# Sheet2.net
KiCad netlist of a schematic drawn in Altium Designer
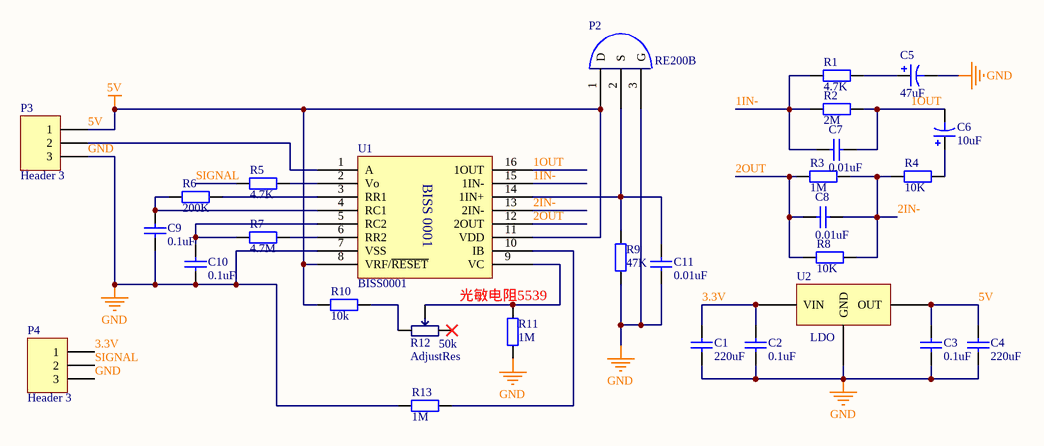
[diagram p0: Sheet2.SchDoc]

(export (version "E")
  (design (tool "Eeschema 10.0.6"))
  (components
    (comp (ref "C1")
      (value "220uF")
      (footprint "8*12")
      (description "Capacitor")
      (fields (field (name "Comment") "Cap") (field (name "PUBLISHER") "Altium Limited"))
      (libsource (lib "Miscellaneous Devices") (part "Cap"))
    )
    (comp (ref "C2")
      (value "0.1uF")
      (footprint "0603")
      (description "Capacitor")
      (fields (field (name "Comment") "Cap") (field (name "PUBLISHER") "Altium Limited"))
      (libsource (lib "Miscellaneous Devices") (part "Cap"))
    )
    (comp (ref "C3")
      (value "0.1uF")
      (footprint "0603")
      (description "Capacitor")
      (fields (field (name "Comment") "Cap") (field (name "PUBLISHER") "Altium Limited"))
      (libsource (lib "Miscellaneous Devices") (part "Cap"))
    )
    (comp (ref "C4")
      (value "220uF")
      (footprint "8*12")
      (description "Capacitor")
      (fields (field (name "Comment") "Cap") (field (name "PUBLISHER") "Altium Limited"))
      (libsource (lib "Miscellaneous Devices") (part "Cap"))
    )
    (comp (ref "C5")
      (value "47uF")
      (footprint "1210")
      (description "Polarized Capacitor (Radial)")
      (fields (field (name "Comment") "Cap Pol1") (field (name "PUBLISHER") "Altium Limited"))
      (libsource (lib "Miscellaneous Devices") (part "Cap Pol1"))
    )
    (comp (ref "C6")
      (value "10uF")
      (footprint "1206")
      (description "Polarized Capacitor (Radial)")
      (fields (field (name "Comment") "Cap Pol1") (field (name "PUBLISHER") "Altium Limited"))
      (libsource (lib "Miscellaneous Devices") (part "Cap Pol1"))
    )
    (comp (ref "C7")
      (value "0.01uF")
      (footprint "0603")
      (description "Capacitor")
      (fields (field (name "Comment") "Cap") (field (name "PUBLISHER") "Altium Limited"))
      (libsource (lib "Miscellaneous Devices") (part "Cap"))
    )
    (comp (ref "C8")
      (value "0.01uF")
      (footprint "0603")
      (description "Capacitor")
      (fields (field (name "Comment") "Cap") (field (name "PUBLISHER") "Altium Limited"))
      (libsource (lib "Miscellaneous Devices") (part "Cap"))
    )
    (comp (ref "C9")
      (value "0.1uF")
      (footprint "0603")
      (description "Capacitor")
      (fields (field (name "Comment") "Cap") (field (name "PUBLISHER") "Altium Limited"))
      (libsource (lib "Miscellaneous Devices") (part "Cap"))
    )
    (comp (ref "C10")
      (value "0.1uF")
      (footprint "0603")
      (description "Capacitor")
      (fields (field (name "Comment") "Cap") (field (name "PUBLISHER") "Altium Limited"))
      (libsource (lib "Miscellaneous Devices") (part "Cap"))
    )
    (comp (ref "C11")
      (value "0.01uF")
      (footprint "0603")
      (description "Capacitor")
      (fields (field (name "Comment") "Cap") (field (name "PUBLISHER") "Altium Limited"))
      (libsource (lib "Miscellaneous Devices") (part "Cap"))
    )
    (comp (ref "P2")
      (value "RE200B")
      (footprint "RE200B")
      (description "Infrared Sensor")
      (libsource (lib "Schlib1") (part "RE200B"))
    )
    (comp (ref "P3")
      (value "Header 3")
      (footprint "HDR1X3")
      (description "Header, 3-Pin")
      (fields (field (name "PUBLISHER") "Altium Limited"))
      (libsource (lib "Miscellaneous Connectors") (part "Header 3"))
    )
    (comp (ref "P4")
      (value "Header 3")
      (footprint "HDR1X3")
      (description "Header, 3-Pin")
      (fields (field (name "PUBLISHER") "Altium Limited"))
      (libsource (lib "Miscellaneous Connectors") (part "Header 3"))
    )
    (comp (ref "R1")
      (value "4.7K")
      (footprint "0603")
      (description "Resistor")
      (fields (field (name "Comment") "Res2") (field (name "PUBLISHER") "Altium Limited"))
      (libsource (lib "") (part "Res2_1"))
    )
    (comp (ref "R2")
      (value "2M")
      (footprint "0603")
      (description "Resistor")
      (fields (field (name "Comment") "Res2") (field (name "PUBLISHER") "Altium Limited"))
      (libsource (lib "") (part "Res2_1"))
    )
    (comp (ref "R3")
      (value "1M")
      (footprint "0603")
      (description "Resistor")
      (fields (field (name "Comment") "Res2") (field (name "PUBLISHER") "Altium Limited"))
      (libsource (lib "") (part "Res2_1"))
    )
    (comp (ref "R4")
      (value "10K")
      (footprint "0603")
      (description "Resistor")
      (fields (field (name "Comment") "Res2") (field (name "PUBLISHER") "Altium Limited"))
      (libsource (lib "") (part "Res2_1"))
    )
    (comp (ref "R5")
      (value "4.7K")
      (footprint "0603")
      (description "Resistor")
      (fields (field (name "Comment") "Res2") (field (name "PUBLISHER") "Altium Limited"))
      (libsource (lib "") (part "Res2_2"))
    )
    (comp (ref "R6")
      (value "200K")
      (footprint "0603")
      (description "Resistor")
      (fields (field (name "Comment") "Res2") (field (name "PUBLISHER") "Altium Limited"))
      (libsource (lib "") (part "Res2_2"))
    )
    (comp (ref "R7")
      (value "4.7M")
      (footprint "0603")
      (description "Resistor")
      (fields (field (name "Comment") "Res2") (field (name "PUBLISHER") "Altium Limited"))
      (libsource (lib "") (part "Res2_2"))
    )
    (comp (ref "R8")
      (value "10K")
      (footprint "0603")
      (description "Resistor")
      (fields (field (name "Comment") "Res2") (field (name "PUBLISHER") "Altium Limited"))
      (libsource (lib "") (part "Res2_1"))
    )
    (comp (ref "R9")
      (value "47K")
      (footprint "0603")
      (description "Resistor")
      (fields (field (name "Comment") "Res2") (field (name "PUBLISHER") "Altium Limited"))
      (libsource (lib "Miscellaneous Devices") (part "Res2"))
    )
    (comp (ref "R10")
      (value "10k")
      (footprint "0603")
      (description "Resistor")
      (fields (field (name "Comment") "Res2") (field (name "PUBLISHER") "Altium Limited"))
      (libsource (lib "") (part "Res2_2"))
    )
    (comp (ref "R11")
      (value "1M")
      (footprint "photoresistor5539")
      (description "Resistor")
      (fields (field (name "Comment") "Res2") (field (name "PUBLISHER") "Altium Limited"))
      (libsource (lib "Miscellaneous Devices") (part "Res2"))
    )
    (comp (ref "R12")
      (value "AdjustRes")
      (footprint "RM063-503")
      (description "RM063-503")
      (fields (field (name "ALTIUM_UNNAMED_1") "50k"))
      (libsource (lib "Schlib1") (part "RM063-503"))
    )
    (comp (ref "R13")
      (value "1M")
      (footprint "0603")
      (description "Resistor")
      (fields (field (name "Comment") "Res2") (field (name "PUBLISHER") "Altium Limited"))
      (libsource (lib "") (part "Res2_2"))
    )
    (comp (ref "U1")
      (value "BISS0001")
      (footprint "BISS0001")
      (description "Infrared Sensor")
      (libsource (lib "Schlib1") (part "BISS0001"))
    )
    (comp (ref "U2")
      (value "LDO")
      (footprint "SOT-89-3")
      (description "+1V~35V >5V")
      (libsource (lib "Schlib1") (part "SE8550"))
    )
  )
  (nets
    (net (code "1") (name "/1IN-") (class "Default")
      (node (ref "C7") (pin "2") (pinfunction "2_2") (pintype "passive"))
      (node (ref "R1") (pin "2") (pinfunction "2_2") (pintype "passive"))
      (node (ref "R2") (pin "2") (pinfunction "2_2") (pintype "passive"))
      (node (ref "U1") (pin "15") (pinfunction "1IN-_15") (pintype "passive"))
    )
    (net (code "2") (name "/1OUT") (class "Default")
      (node (ref "C6") (pin "2") (pinfunction "2_2") (pintype "passive"))
      (node (ref "C7") (pin "1") (pinfunction "1_1") (pintype "passive"))
      (node (ref "R2") (pin "1") (pinfunction "1_1") (pintype "passive"))
      (node (ref "U1") (pin "16") (pinfunction "1OUT_16") (pintype "passive"))
    )
    (net (code "3") (name "/2IN-") (class "Default")
      (node (ref "C8") (pin "1") (pinfunction "1_1") (pintype "passive"))
      (node (ref "R3") (pin "1") (pinfunction "1_1") (pintype "passive"))
      (node (ref "R4") (pin "2") (pinfunction "2_2") (pintype "passive"))
      (node (ref "R8") (pin "1") (pinfunction "1_1") (pintype "passive"))
      (node (ref "U1") (pin "13") (pinfunction "2IN-_13") (pintype "passive"))
    )
    (net (code "4") (name "/2OUT") (class "Default")
      (node (ref "C8") (pin "2") (pinfunction "2_2") (pintype "passive"))
      (node (ref "R3") (pin "2") (pinfunction "2_2") (pintype "passive"))
      (node (ref "R8") (pin "2") (pinfunction "2_2") (pintype "passive"))
      (node (ref "U1") (pin "12") (pinfunction "2OUT_12") (pintype "passive"))
    )
    (net (code "5") (name "/3.3V") (class "Default")
      (node (ref "C1") (pin "1") (pinfunction "1_1") (pintype "passive"))
      (node (ref "C2") (pin "1") (pinfunction "1_1") (pintype "passive"))
      (node (ref "P4") (pin "1") (pinfunction "1_1") (pintype "passive"))
      (node (ref "U2") (pin "2") (pinfunction "VIN_2") (pintype "passive"))
    )
    (net (code "6") (name "/SIGNAL") (class "Default")
      (node (ref "P4") (pin "2") (pinfunction "2_2") (pintype "passive"))
      (node (ref "R5") (pin "1") (pinfunction "1_1") (pintype "passive"))
    )
    (net (code "7") (name "5V") (class "Default")
      (node (ref "C3") (pin "1") (pinfunction "1_1") (pintype "passive"))
      (node (ref "C4") (pin "1") (pinfunction "1_1") (pintype "passive"))
      (node (ref "P2") (pin "1") (pinfunction "D_1") (pintype "passive"))
      (node (ref "P3") (pin "1") (pinfunction "1_1") (pintype "passive"))
      (node (ref "R10") (pin "1") (pinfunction "1_1") (pintype "passive"))
      (node (ref "U1") (pin "11") (pinfunction "VDD_11") (pintype "passive"))
      (node (ref "U1") (pin "8") (pinfunction "VRF/~{RESET}_8") (pintype "passive"))
      (node (ref "U2") (pin "3") (pinfunction "OUT_3") (pintype "passive"))
    )
    (net (code "8") (name "GND") (class "Default")
      (node (ref "C1") (pin "2") (pinfunction "2_2") (pintype "passive"))
      (node (ref "C10") (pin "2") (pinfunction "2_2") (pintype "passive"))
      (node (ref "C11") (pin "1") (pinfunction "1_1") (pintype "passive"))
      (node (ref "C2") (pin "2") (pinfunction "2_2") (pintype "passive"))
      (node (ref "C3") (pin "2") (pinfunction "2_2") (pintype "passive"))
      (node (ref "C4") (pin "2") (pinfunction "2_2") (pintype "passive"))
      (node (ref "C5") (pin "2") (pinfunction "2_2") (pintype "passive"))
      (node (ref "C9") (pin "2") (pinfunction "2_2") (pintype "passive"))
      (node (ref "P2") (pin "3") (pinfunction "G_3") (pintype "passive"))
      (node (ref "P3") (pin "3") (pinfunction "3_3") (pintype "passive"))
      (node (ref "P4") (pin "3") (pinfunction "3_3") (pintype "passive"))
      (node (ref "R11") (pin "1") (pinfunction "1_1") (pintype "passive"))
      (node (ref "R13") (pin "1") (pinfunction "1_1") (pintype "passive"))
      (node (ref "R9") (pin "1") (pinfunction "1_1") (pintype "passive"))
      (node (ref "U1") (pin "7") (pinfunction "VSS_7") (pintype "passive"))
      (node (ref "U2") (pin "1") (pinfunction "GND_1") (pintype "passive"))
    )
    (net (code "9") (name "Net-(C5-Pad1)") (class "Default")
      (node (ref "C5") (pin "1") (pinfunction "1_1") (pintype "passive"))
      (node (ref "R1") (pin "1") (pinfunction "1_1") (pintype "passive"))
    )
    (net (code "10") (name "Net-(C6-Pad1)") (class "Default")
      (node (ref "C6") (pin "1") (pinfunction "1_1") (pintype "passive"))
      (node (ref "R4") (pin "1") (pinfunction "1_1") (pintype "passive"))
    )
    (net (code "11") (name "Net-(P2-S)") (class "Default")
      (node (ref "C11") (pin "2") (pinfunction "2_2") (pintype "passive"))
      (node (ref "P2") (pin "2") (pinfunction "S_2") (pintype "passive"))
      (node (ref "R9") (pin "2") (pinfunction "2_2") (pintype "passive"))
      (node (ref "U1") (pin "14") (pinfunction "1IN+_14") (pintype "passive"))
    )
    (net (code "12") (name "Net-(R10-Pad2)") (class "Default")
      (node (ref "R10") (pin "2") (pinfunction "2_2") (pintype "passive"))
      (node (ref "R12") (pin "1") (pintype "passive"))
    )
    (net (code "13") (name "Net-(U1-A)") (class "Default")
      (node (ref "P3") (pin "2") (pinfunction "2_2") (pintype "passive"))
      (node (ref "U1") (pin "1") (pinfunction "A_1") (pintype "passive"))
    )
    (net (code "14") (name "Net-(U1-IB)") (class "Default")
      (node (ref "R13") (pin "2") (pinfunction "2_2") (pintype "passive"))
      (node (ref "U1") (pin "10") (pinfunction "IB_10") (pintype "passive"))
    )
    (net (code "15") (name "Net-(U1-RC1)") (class "Default")
      (node (ref "C9") (pin "1") (pinfunction "1_1") (pintype "passive"))
      (node (ref "R6") (pin "1") (pinfunction "1_1") (pintype "passive"))
      (node (ref "U1") (pin "4") (pinfunction "RC1_4") (pintype "passive"))
    )
    (net (code "16") (name "Net-(U1-RC2)") (class "Default")
      (node (ref "C10") (pin "1") (pinfunction "1_1") (pintype "passive"))
      (node (ref "R7") (pin "1") (pinfunction "1_1") (pintype "passive"))
      (node (ref "U1") (pin "5") (pinfunction "RC2_5") (pintype "passive"))
    )
    (net (code "17") (name "Net-(U1-RR1)") (class "Default")
      (node (ref "R6") (pin "2") (pinfunction "2_2") (pintype "passive"))
      (node (ref "U1") (pin "3") (pinfunction "RR1_3") (pintype "passive"))
    )
    (net (code "18") (name "Net-(U1-RR2)") (class "Default")
      (node (ref "R7") (pin "2") (pinfunction "2_2") (pintype "passive"))
      (node (ref "U1") (pin "6") (pinfunction "RR2_6") (pintype "passive"))
    )
    (net (code "19") (name "Net-(U1-VC)") (class "Default")
      (node (ref "R11") (pin "2") (pinfunction "2_2") (pintype "passive"))
      (node (ref "R12") (pin "2") (pinfunction "2_2") (pintype "passive"))
      (node (ref "U1") (pin "9") (pinfunction "VC_9") (pintype "passive"))
    )
    (net (code "20") (name "Net-(U1-Vo)") (class "Default")
      (node (ref "R5") (pin "2") (pinfunction "2_2") (pintype "passive"))
      (node (ref "U1") (pin "2") (pinfunction "Vo_2") (pintype "passive"))
    )
    (net (code "21") (name "unconnected-(R12-Pad3)") (class "Default")
      (node (ref "R12") (pin "3") (pinfunction "3_3") (pintype "passive+no_connect"))
    )
  )
)
